# Gastroscopy-Tool-Input.net
KiCad netlist of a schematic drawn in Altium Designer
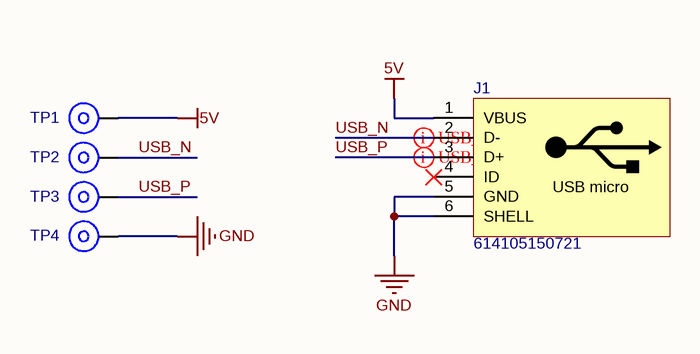
[diagram p0: Gastroscopy-Tool-Input.SchDoc]

(export (version "E")
  (design (tool "Eeschema 10.0.6"))
  (components
    (comp (ref "J1")
      (value "614105150721")
      (footprint "614105150721")
      (description "CONN RCPT USB2.0 MICRO B VERT")
      (libsource (lib "Gastroscopy-Tool") (part "614105150721"))
    )
    (comp (ref "TP1")
      (value "TEST_POINT_TH")
      (footprint "TEST_POINT_TH")
      (description "TH TETS POINT")
      (libsource (lib "Gastroscopy-Tool") (part "TEST_POINT_TH"))
    )
    (comp (ref "TP2")
      (value "TEST_POINT_TH")
      (footprint "TEST_POINT_TH")
      (description "TH TETS POINT")
      (libsource (lib "Gastroscopy-Tool") (part "TEST_POINT_TH"))
    )
    (comp (ref "TP3")
      (value "TEST_POINT_TH")
      (footprint "TEST_POINT_TH")
      (description "TH TETS POINT")
      (libsource (lib "Gastroscopy-Tool") (part "TEST_POINT_TH"))
    )
    (comp (ref "TP4")
      (value "TEST_POINT_TH")
      (footprint "TEST_POINT_TH")
      (description "TH TETS POINT")
      (libsource (lib "Gastroscopy-Tool") (part "TEST_POINT_TH"))
    )
  )
  (nets
    (net (code "1") (name "/USB_N") (class "Default")
      (node (ref "J1") (pin "2") (pinfunction "D-_2") (pintype "passive"))
      (node (ref "TP2") (pin "1") (pinfunction "1_1") (pintype "passive"))
    )
    (net (code "2") (name "/USB_P") (class "Default")
      (node (ref "J1") (pin "3") (pinfunction "D+_3") (pintype "passive"))
      (node (ref "TP3") (pin "1") (pinfunction "1_1") (pintype "passive"))
    )
    (net (code "3") (name "5V") (class "Default")
      (node (ref "J1") (pin "1") (pinfunction "VBUS_1") (pintype "passive"))
      (node (ref "TP1") (pin "1") (pinfunction "1_1") (pintype "passive"))
    )
    (net (code "4") (name "GND") (class "Default")
      (node (ref "J1") (pin "5") (pinfunction "GND_5") (pintype "passive"))
      (node (ref "J1") (pin "6") (pinfunction "SHELL_6") (pintype "passive"))
      (node (ref "TP4") (pin "1") (pinfunction "1_1") (pintype "passive"))
    )
    (net (code "5") (name "unconnected-(J1-ID-Pad4)") (class "Default")
      (node (ref "J1") (pin "4") (pinfunction "ID_4") (pintype "passive+no_connect"))
    )
  )
)
